# 1-Schematic_controle_ar_morpheus.net
KiCad netlist of a schematic drawn in EasyEDA
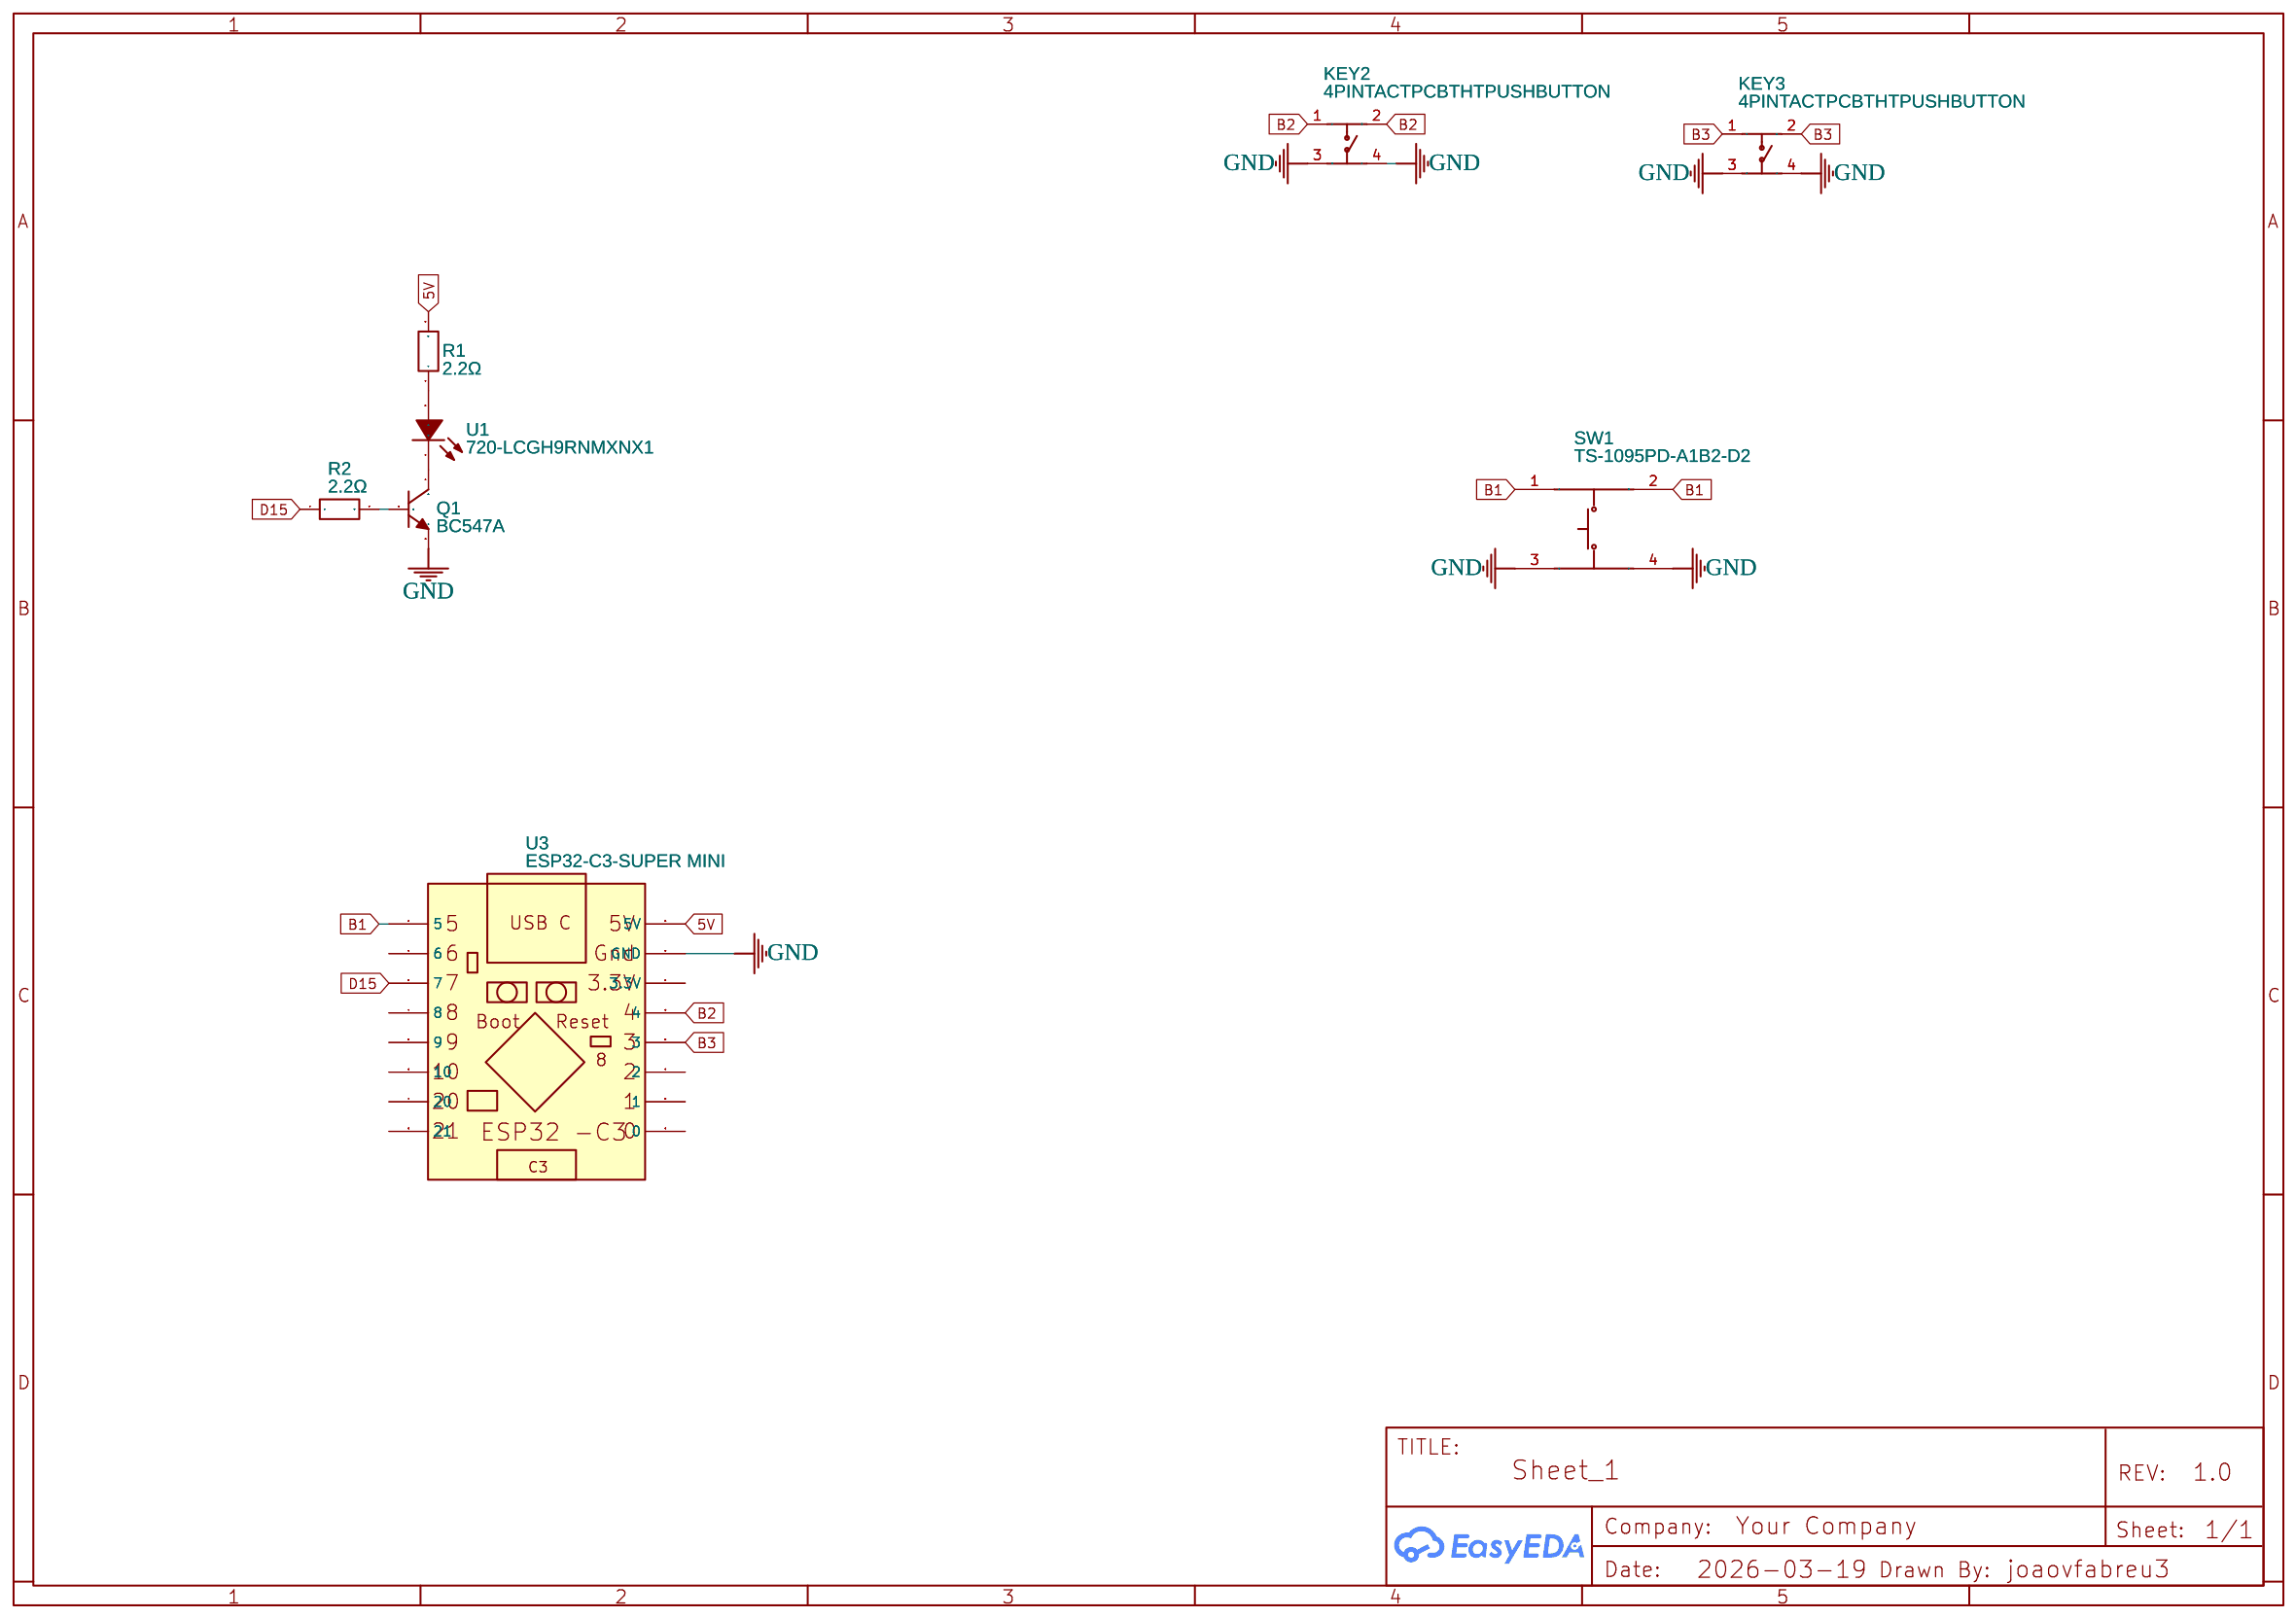
[diagram p0: schematic sheet]

(export (version "E")
  (design (tool "Eeschema 10.0.6"))
  (components
    (comp (ref "KEY2")
      (value "4PINTACTPCBTHTPUSHBUTTON")
      (fields (field (name "Manufacturer Part") "4pinTACTPCBTHTPushButton"))
      (libsource (lib "") (part "4PINTACTPCBTHTPUSHBUTTON"))
    )
    (comp (ref "KEY3")
      (value "4PINTACTPCBTHTPUSHBUTTON")
      (fields (field (name "Manufacturer Part") "4pinTACTPCBTHTPushButton"))
      (libsource (lib "") (part "4PINTACTPCBTHTPUSHBUTTON"))
    )
    (comp (ref "Q1")
      (value "BC547A")
      (fields (field (name "Manufacturer") "onsemi(安森美)"))
      (libsource (lib "") (part "BC547A"))
    )
    (comp (ref "R1")
      (value "2.2Ω")
      (fields
        (field (name "Manufacturer Part") "CERAMIC RESISTOR 10W/ 2,2 OHM")
        (field (name "Manufacturer") "Visaton")
      )
      (libsource (lib "") (part "CERAMIC RESISTOR 10W/ 2,2 OHM"))
    )
    (comp (ref "R2")
      (value "2.2Ω")
      (fields
        (field (name "Manufacturer Part") "CERAMIC RESISTOR 10W/ 2,2 OHM")
        (field (name "Manufacturer") "Visaton")
      )
      (libsource (lib "") (part "CERAMIC RESISTOR 10W/ 2,2 OHM_1"))
    )
    (comp (ref "SW1")
      (value "TS-1095PD-A1B2-D2")
      (fields (field (name "Manufacturer") "Yuandi(元迪)"))
      (libsource (lib "") (part "TS-1095PD-A1B2-D2"))
    )
    (comp (ref "U1") (value "720-LCGH9RNMXNX1") (libsource (lib "") (part "720-LCGH9RNMXNX1")))
    (comp (ref "U3") (value "ESP32-C3-SUPER MINI") (libsource (lib "") (part "ESP32-C3-SUPER MINI")))
  )
  (nets
    (net (code "1") (name "5V") (class "Default")
      (node (ref "R1") (pin "2") (pinfunction "2_2") (pintype "unspecified"))
      (node (ref "U3") (pin "16") (pinfunction "5V_16") (pintype "passive"))
    )
    (net (code "2") (name "B1") (class "Default")
      (node (ref "SW1") (pin "1") (pinfunction "1_1") (pintype "unspecified"))
      (node (ref "SW1") (pin "2") (pinfunction "2_2") (pintype "unspecified"))
      (node (ref "U3") (pin "1") (pinfunction "5_1") (pintype "bidirectional"))
    )
    (net (code "3") (name "B2") (class "Default")
      (node (ref "KEY2") (pin "1") (pinfunction "1_1") (pintype "unspecified"))
      (node (ref "KEY2") (pin "2") (pinfunction "2_2") (pintype "unspecified"))
      (node (ref "U3") (pin "13") (pinfunction "4_13") (pintype "bidirectional"))
    )
    (net (code "4") (name "B3") (class "Default")
      (node (ref "KEY3") (pin "1") (pinfunction "1_1") (pintype "unspecified"))
      (node (ref "KEY3") (pin "2") (pinfunction "2_2") (pintype "unspecified"))
      (node (ref "U3") (pin "12") (pinfunction "3_12") (pintype "bidirectional"))
    )
    (net (code "5") (name "D15") (class "Default")
      (node (ref "R2") (pin "1") (pinfunction "1_1") (pintype "unspecified"))
      (node (ref "U3") (pin "3") (pinfunction "7_3") (pintype "bidirectional"))
    )
    (net (code "6") (name "GND") (class "Default")
      (node (ref "KEY2") (pin "3") (pinfunction "3_3") (pintype "unspecified"))
      (node (ref "KEY2") (pin "4") (pinfunction "4_4") (pintype "unspecified"))
      (node (ref "KEY3") (pin "3") (pinfunction "3_3") (pintype "unspecified"))
      (node (ref "KEY3") (pin "4") (pinfunction "4_4") (pintype "unspecified"))
      (node (ref "Q1") (pin "3") (pinfunction "E_3") (pintype "input"))
      (node (ref "SW1") (pin "3") (pinfunction "3_3") (pintype "unspecified"))
      (node (ref "SW1") (pin "4") (pinfunction "4_4") (pintype "unspecified"))
      (node (ref "U3") (pin "15") (pinfunction "GND_15") (pintype "passive"))
    )
    (net (code "7") (name "Net-(Q1-B)") (class "Default")
      (node (ref "Q1") (pin "2") (pinfunction "B_2") (pintype "input"))
      (node (ref "R2") (pin "2") (pinfunction "2_2") (pintype "unspecified"))
    )
    (net (code "8") (name "Net-(Q1-C)") (class "Default")
      (node (ref "Q1") (pin "1") (pinfunction "C_1") (pintype "input"))
      (node (ref "U1") (pin "1") (pinfunction "K_1") (pintype "unspecified"))
    )
    (net (code "9") (name "Net-(U1-A)") (class "Default")
      (node (ref "R1") (pin "1") (pinfunction "1_1") (pintype "unspecified"))
      (node (ref "U1") (pin "2") (pinfunction "A_2") (pintype "unspecified"))
    )
    (net (code "10") (name "unconnected-(U3-0-Pad9)") (class "Default")
      (node (ref "U3") (pin "9") (pinfunction "0_9") (pintype "bidirectional"))
    )
    (net (code "11") (name "unconnected-(U3-1-Pad10)") (class "Default")
      (node (ref "U3") (pin "10") (pinfunction "1_10") (pintype "bidirectional"))
    )
    (net (code "12") (name "unconnected-(U3-2-Pad11)") (class "Default")
      (node (ref "U3") (pin "11") (pinfunction "2_11") (pintype "bidirectional"))
    )
    (net (code "13") (name "unconnected-(U3-3.3V-Pad14)") (class "Default")
      (node (ref "U3") (pin "14") (pinfunction "3.3V_14") (pintype "passive"))
    )
    (net (code "14") (name "unconnected-(U3-6-Pad2)") (class "Default")
      (node (ref "U3") (pin "2") (pinfunction "6_2") (pintype "bidirectional"))
    )
    (net (code "15") (name "unconnected-(U3-8-Pad4)") (class "Default")
      (node (ref "U3") (pin "4") (pinfunction "8_4") (pintype "bidirectional"))
    )
    (net (code "16") (name "unconnected-(U3-9-Pad5)") (class "Default")
      (node (ref "U3") (pin "5") (pinfunction "9_5") (pintype "bidirectional"))
    )
    (net (code "17") (name "unconnected-(U3-10-Pad6)") (class "Default")
      (node (ref "U3") (pin "6") (pinfunction "10_6") (pintype "unspecified"))
    )
    (net (code "18") (name "unconnected-(U3-20-Pad7)") (class "Default")
      (node (ref "U3") (pin "7") (pinfunction "20_7") (pintype "bidirectional"))
    )
    (net (code "19") (name "unconnected-(U3-21-Pad8)") (class "Default")
      (node (ref "U3") (pin "8") (pinfunction "21_8") (pintype "bidirectional"))
    )
  )
)
